# USBC_PD_SOURCING.net
KiCad netlist of a schematic drawn in Altium Designer
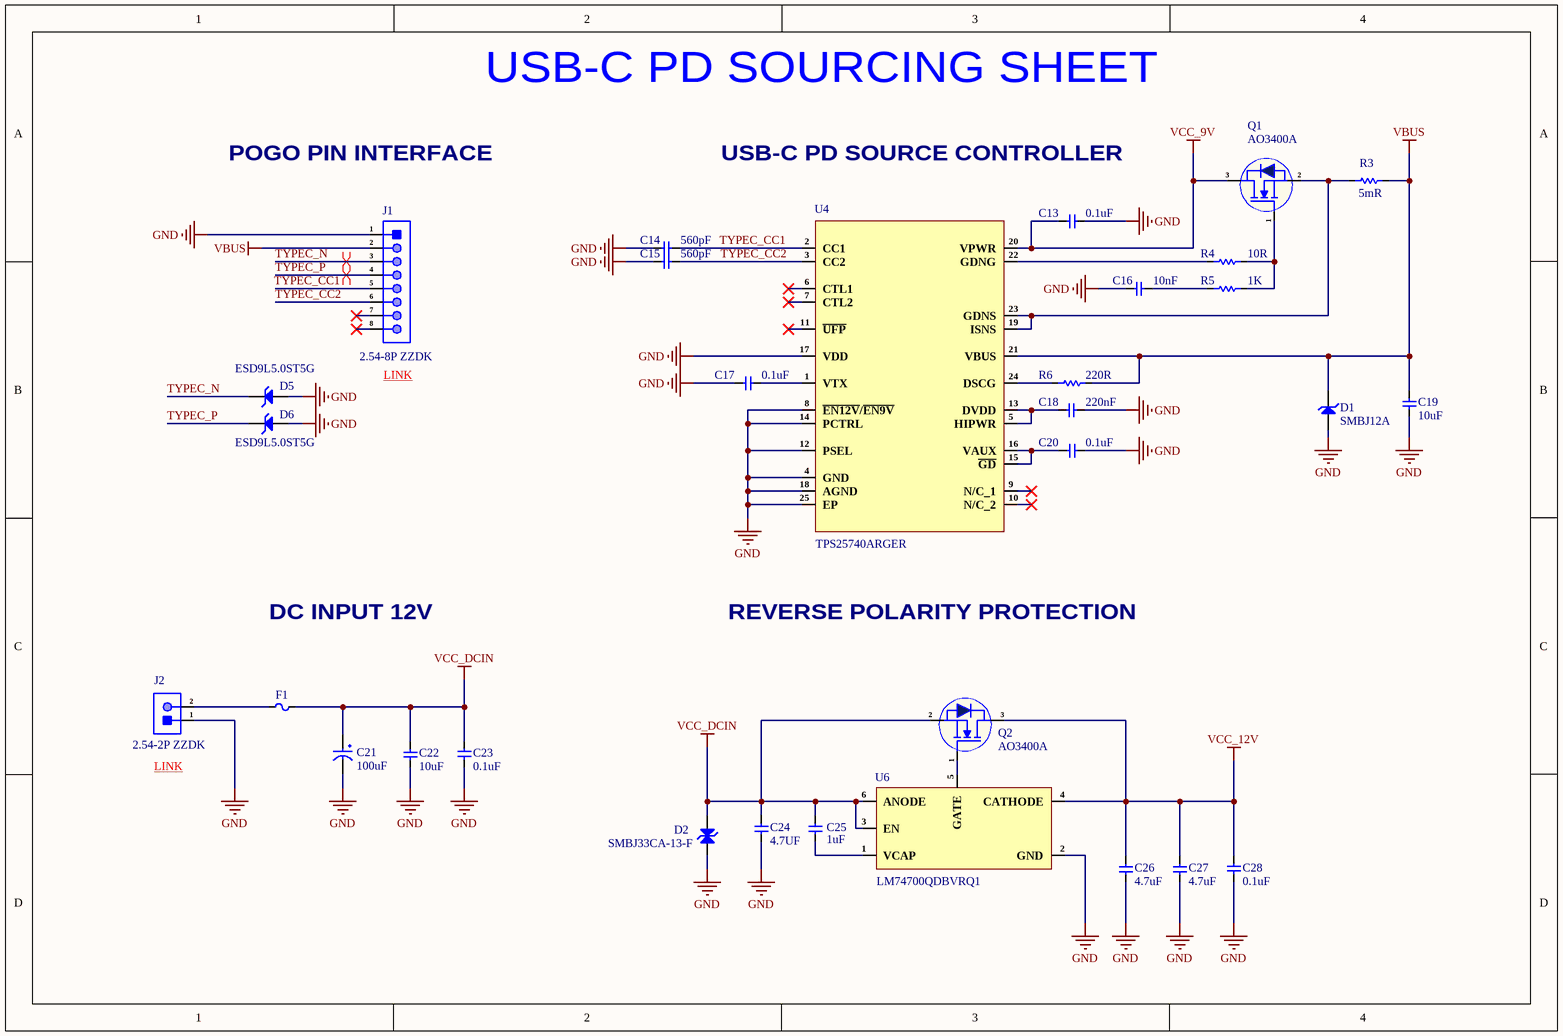
[diagram p0: USBC_PD_SOURCING.SchDoc]

(export (version "E")
  (design (tool "Eeschema 10.0.6"))
  (components
    (comp (ref "C13")
      (value "0.1uF")
      (footprint "Cap-0402")
      (description "CAP CER 0.1UF 50V X7R 0402")
      (fields
        (field (name "MANUFACTURER") "Samsung")
        (field (name "MANUFACTURER PART NUMBER") "CL05B104KB54PNC")
      )
      (libsource (lib "eSpark Libraries") (part "CL05B104KB54PNC"))
    )
    (comp (ref "C14")
      (value "560pF")
      (footprint "Cap-0402")
      (description "CAP CER 560PF 50V X7R 0402")
      (fields
        (field (name "MANUFACTURER") "Yageo")
        (field (name "MANUFACTURER PART NUMBER") "CC0402JRX7R9BB561")
      )
      (libsource (lib "eSpark Libraries") (part "CC0402JRX7R9BB561"))
    )
    (comp (ref "C15")
      (value "560pF")
      (footprint "Cap-0402")
      (description "CAP CER 560PF 50V X7R 0402")
      (fields
        (field (name "MANUFACTURER") "Yageo")
        (field (name "MANUFACTURER PART NUMBER") "CC0402JRX7R9BB561")
      )
      (libsource (lib "eSpark Libraries") (part "CC0402JRX7R9BB561"))
    )
    (comp (ref "C16")
      (value "10nF")
      (footprint "Cap-0402")
      (description "CAP CER 10000PF 50V X7R 0402")
      (fields
        (field (name "MANUFACTURER") "Yageo")
        (field (name "MANUFACTURER PART NUMBER") "CC0402KRX7R9BB103")
      )
      (libsource (lib "eSpark Libraries") (part "CC0402KRX7R9BB103"))
    )
    (comp (ref "C17")
      (value "0.1uF")
      (footprint "Cap-0402")
      (description "CAP CER 0.1UF 50V X7R 0402")
      (fields
        (field (name "MANUFACTURER") "Samsung")
        (field (name "MANUFACTURER PART NUMBER") "CL05B104KB54PNC")
      )
      (libsource (lib "eSpark Libraries") (part "CL05B104KB54PNC"))
    )
    (comp (ref "C18")
      (value "220nF")
      (footprint "Cap-0402")
      (description "CAP CER 0.22UF 25V X5R 0402")
      (fields
        (field (name "MANUFACTURER") "Yageo")
        (field (name "MANUFACTURER PART NUMBER") "CC0402KRX5R8BB224")
      )
      (libsource (lib "eSpark Libraries") (part "CC0402KRX5R8BB224"))
    )
    (comp (ref "C19")
      (value "10uF")
      (footprint "Cap-0805")
      (description "CAP CER 10UF 50V X5R 0805")
      (fields
        (field (name "MANUFACTURER") "Murata")
        (field (name "MANUFACTURER PART NUMBER") "GRM21BR61H106ME43L")
      )
      (libsource (lib "eSpark Libraries") (part "GRM21BR61H106ME43L"))
    )
    (comp (ref "C20")
      (value "0.1uF")
      (footprint "Cap-0402")
      (description "CAP CER 0.1UF 50V X7R 0402")
      (fields
        (field (name "MANUFACTURER") "Samsung")
        (field (name "MANUFACTURER PART NUMBER") "CL05B104KB54PNC")
      )
      (libsource (lib "eSpark Libraries") (part "CL05B104KB54PNC"))
    )
    (comp (ref "C21")
      (value "100uF")
      (footprint "Case-E")
      (description "CAP TANT 100UF 20% 25V 2917")
      (fields
        (field (name "MANUFACTURER") "Kyocera AVX")
        (field (name "MANUFACTURER PART NUMBER") "TAJE107M025RNJ")
      )
      (libsource (lib "eSpark Libraries") (part "TAJE107M025RNJ"))
    )
    (comp (ref "C22")
      (value "10uF")
      (footprint "Cap-0805")
      (description "CAP CER 10UF 50V X5R 0805")
      (fields
        (field (name "MANUFACTURER") "Murata")
        (field (name "MANUFACTURER PART NUMBER") "GRM21BR61H106ME43L")
      )
      (libsource (lib "eSpark Libraries") (part "GRM21BR61H106ME43L"))
    )
    (comp (ref "C23")
      (value "0.1uF")
      (footprint "Cap-0402")
      (description "CAP CER 0.1UF 50V X7R 0402")
      (fields
        (field (name "MANUFACTURER") "Samsung")
        (field (name "MANUFACTURER PART NUMBER") "CL05B104KB54PNC")
      )
      (libsource (lib "eSpark Libraries") (part "CL05B104KB54PNC"))
    )
    (comp (ref "C24")
      (value "4.7UF")
      (footprint "Cap-0603")
      (description "CAP CER 4.7UF 25V X5R 0603")
      (fields
        (field (name "MANUFACTURER") "Samsung")
        (field (name "MANUFACTURER PART NUMBER") "CL10A475KA8NQNC")
      )
      (libsource (lib "eSpark Libraries") (part "CL10A475KA8NQNC"))
    )
    (comp (ref "C25")
      (value "1uF")
      (footprint "Cap-0402")
      (description "CAP CER 1UF 25V X5R 0402")
      (fields
        (field (name "MANUFACTURER") "Yageo")
        (field (name "MANUFACTURER PART NUMBER") "CC0402KRX5R8BB105")
      )
      (libsource (lib "eSpark Libraries") (part "CC0402KRX5R8BB105"))
    )
    (comp (ref "C26")
      (value "4.7uF")
      (footprint "Cap-0805")
      (description "CAP CER 4.7UF 50V X5R 0805")
      (fields
        (field (name "MANUFACTURER") "Murata")
        (field (name "MANUFACTURER PART NUMBER") "GRM21BR61H475KE51L")
      )
      (libsource (lib "eSpark Libraries") (part "GRM21BR61H475KE51L"))
    )
    (comp (ref "C27")
      (value "4.7uF")
      (footprint "Cap-0805")
      (description "CAP CER 4.7UF 50V X5R 0805")
      (fields
        (field (name "MANUFACTURER") "Murata")
        (field (name "MANUFACTURER PART NUMBER") "GRM21BR61H475KE51L")
      )
      (libsource (lib "eSpark Libraries") (part "GRM21BR61H475KE51L"))
    )
    (comp (ref "C28")
      (value "0.1uF")
      (footprint "Cap-0402")
      (description "CAP CER 0.1UF 50V X7R 0402")
      (fields
        (field (name "MANUFACTURER") "Samsung")
        (field (name "MANUFACTURER PART NUMBER") "CL05B104KB54PNC")
      )
      (libsource (lib "eSpark Libraries") (part "CL05B104KB54PNC"))
    )
    (comp (ref "D1")
      (value "SMBJ12A")
      (footprint "SMB_")
      (description "TVS DIODE 12VWM 19.9VC DO214AA")
      (fields (field (name "LCSC PART NUMBER") "C151251") (field (name "MANUFACTURER") "Littelfuse"))
      (libsource (lib "eSpark Libraries") (part "SMBJ12A"))
    )
    (comp (ref "D2")
      (value "SMBJ33CA-13-F")
      (footprint "SMB Bi Directional")
      (description "TVS DIODE 33VWM 53.3VC SMB")
      (fields (field (name "MANUFACTURER") "Diodes") (field (name "LCSC PART NUMBER") "C135068"))
      (libsource (lib "eSpark Libraries") (part "SMBJ33CA-13-F"))
    )
    (comp (ref "D5")
      (value "ESD9L5.0ST5G")
      (footprint "SOD-923.")
      (fields (field (name "MANUFACTURER") "ON Semiconductor") (field (name "LCSC PART NUMBER") "C82326"))
      (libsource (lib "eSpark Libraries") (part "ESD9L5.0ST5G"))
    )
    (comp (ref "D6")
      (value "ESD9L5.0ST5G")
      (footprint "SOD-923.")
      (description "TVS DIODE 5V 9.8V SOD923")
      (fields (field (name "MANUFACTURER") "ON Semiconductor") (field (name "LCSC PART NUMBER") "C82326"))
      (libsource (lib "eSpark Libraries") (part "ESD9L5.0ST5G"))
    )
    (comp (ref "F1")
      (value "BSMD1812-300-24V")
      (footprint "Fuse-1812_")
      (description "24V 3A 40A 6A 1812 Resettable Fuses ROHS")
      (fields (field (name "LCSC PART NUMBER") "C7500481") (field (name "MANUFACTURER") "BHFUSE"))
      (libsource (lib "eSpark Libraries") (part "BSMD1812-300-24V"))
    )
    (comp (ref "J1")
      (value "2.54-8P ZZDK")
      (footprint "2.54-8P ZZDK")
      (fields (field (name "MANUFACTURER") "SHOU HAN") (field (name "LCSC PART NUMBER") "C18185655"))
      (libsource (lib "DOCK_ESP32_v1.0") (part "2.54-8P ZZDK"))
    )
    (comp (ref "J2")
      (value "2.54-2P ZZDK")
      (footprint "2.54-2P ZZDK")
      (fields (field (name "MANUFACTURER") "SHOU HAN") (field (name "LCSC PART NUMBER") "C18185649"))
      (libsource (lib "eSpark Libraries") (part "2.54-2P ZZDK"))
    )
    (comp (ref "Q1")
      (value "AO3400A")
      (footprint "sot-23")
      (description "30V 5.8A 32mΩ@10V,5.8A 1.4W 1.4V@250uA N Channel SOT-23 MOSFETs ROHS")
      (fields (field (name "MANUFACTURER") "BORN") (field (name "LCSC PART NUMBER") "C344010"))
      (libsource (lib "eSpark Libraries") (part "AO3400A"))
    )
    (comp (ref "Q2")
      (value "AO3400A")
      (footprint "sot-23")
      (description "30V 5.8A 32mΩ@10V,5.8A 1.4W 1.4V@250uA N Channel SOT-23 MOSFETs ROHS")
      (fields (field (name "MANUFACTURER") "BORN") (field (name "LCSC PART NUMBER") "C344010"))
      (libsource (lib "eSpark Libraries") (part "AO3400A"))
    )
    (comp (ref "R3")
      (value "5mR")
      (footprint "RES-2512")
      (description "RES 0.005 OHM 1% 2W 2512")
      (fields (field (name "LCSC PART NUMBER") "C309526") (field (name "MANUFACTURER") "Yageo"))
      (libsource (lib "eSpark Libraries") (part "PA2512FKF7W0R005E"))
    )
    (comp (ref "R4")
      (value "10R")
      (footprint "Res-0603")
      (description "RES SMD 10 OHM 1% 1/10W 0603")
      (fields
        (field (name "MANUFACTURER") "Yageo")
        (field (name "MANUFACTURER PART NUMBER") "RC0603FR-0710RL")
      )
      (libsource (lib "eSpark Libraries") (part "RC0603FR-0710RL"))
    )
    (comp (ref "R5")
      (value "1K")
      (footprint "Res-0402")
      (description "RES SMD 1K OHM 1% 1/5W 0402")
      (fields
        (field (name "MANUFACTURER") "Vishay Dale")
        (field (name "MANUFACTURER PART NUMBER") "CRCW04021K00FKEDHP")
      )
      (libsource (lib "eSpark Libraries") (part "CRCW04021K00FKEDHP"))
    )
    (comp (ref "R6")
      (value "220R")
      (footprint "Res-0402")
      (description "RES 220 OHM 1% 1/16W 0402")
      (fields (field (name "LCSC PART NUMBER") "C112291") (field (name "MANUFACTURER") "Yageo"))
      (libsource (lib "eSpark Libraries") (part "RC0402FR-07220RL"))
    )
    (comp (ref "U4")
      (value "TPS25740ARGER")
      (footprint "QFN50P400X400X100-25N-D")
      (description "TPS25740A USB Type-C Rev 1.2 and USB PD 2.0 Source Controller (5V/9V/15V)")
      (fields (field (name "LCSC PART NUMBER") "C544309"))
      (libsource (lib "DOCK_ESP32_v1.0") (part "TPS25740ARGER"))
    )
    (comp (ref "U6")
      (value "LM74700QDBVRQ1")
      (footprint "SOT-23-6")
      (description "OR Controller N+1 ORing Controller N-Channel 1:1 SOT-23-6")
      (fields (field (name "MANUFACTURER") "Texas Instruments") (field (name "LCSC PART NUMBER") "C2941042"))
      (libsource (lib "eSpark Libraries") (part "LM74700QDBVRQ1"))
    )
  )
  (nets
    (net (code "1") (name "/TYPEC_CC1") (class "Default")
      (node (ref "C14") (pin "2") (pinfunction "2_2") (pintype "passive"))
      (node (ref "J1") (pin "5") (pinfunction "5_5") (pintype "passive"))
      (node (ref "U4") (pin "2") (pinfunction "CC1_2") (pintype "passive"))
    )
    (net (code "2") (name "/TYPEC_CC2") (class "Default")
      (node (ref "C15") (pin "2") (pinfunction "2_2") (pintype "passive"))
      (node (ref "J1") (pin "6") (pinfunction "6_6") (pintype "passive"))
      (node (ref "U4") (pin "3") (pinfunction "CC2_3") (pintype "passive"))
    )
    (net (code "3") (name "/TYPEC_N") (class "Default")
      (node (ref "D5") (pin "1") (pinfunction "K_1") (pintype "passive"))
      (node (ref "J1") (pin "3") (pinfunction "3_3") (pintype "passive"))
    )
    (net (code "4") (name "/TYPEC_P") (class "Default")
      (node (ref "D6") (pin "1") (pinfunction "K_1") (pintype "passive"))
      (node (ref "J1") (pin "4") (pinfunction "4_4") (pintype "passive"))
    )
    (net (code "5") (name "GND") (class "Default")
      (node (ref "C13") (pin "1") (pinfunction "1_1") (pintype "passive"))
      (node (ref "C14") (pin "1") (pinfunction "1_1") (pintype "passive"))
      (node (ref "C15") (pin "1") (pinfunction "1_1") (pintype "passive"))
      (node (ref "C16") (pin "1") (pinfunction "1_1") (pintype "passive"))
      (node (ref "C17") (pin "2") (pinfunction "2_2") (pintype "passive"))
      (node (ref "C18") (pin "2") (pinfunction "2_2") (pintype "passive"))
      (node (ref "C19") (pin "1") (pinfunction "1_1") (pintype "passive"))
      (node (ref "C20") (pin "1") (pinfunction "1_1") (pintype "passive"))
      (node (ref "C21") (pin "2") (pinfunction "2_2") (pintype "passive"))
      (node (ref "C22") (pin "1") (pinfunction "1_1") (pintype "passive"))
      (node (ref "C23") (pin "2") (pinfunction "2_2") (pintype "passive"))
      (node (ref "C24") (pin "1") (pinfunction "1_1") (pintype "passive"))
      (node (ref "C26") (pin "1") (pinfunction "1_1") (pintype "passive"))
      (node (ref "C27") (pin "1") (pinfunction "1_1") (pintype "passive"))
      (node (ref "C28") (pin "2") (pinfunction "2_2") (pintype "passive"))
      (node (ref "D1") (pin "1") (pinfunction "A_1") (pintype "passive"))
      (node (ref "D2") (pin "1") (pinfunction "A_1") (pintype "passive"))
      (node (ref "D5") (pin "2") (pinfunction "A_2") (pintype "passive"))
      (node (ref "D6") (pin "2") (pinfunction "A_2") (pintype "passive"))
      (node (ref "J1") (pin "1") (pinfunction "1_1") (pintype "passive"))
      (node (ref "J2") (pin "1") (pinfunction "1_1") (pintype "passive"))
      (node (ref "U4") (pin "12") (pinfunction "PSEL_12") (pintype "passive"))
      (node (ref "U4") (pin "14") (pinfunction "PCTRL_14") (pintype "passive"))
      (node (ref "U4") (pin "17") (pinfunction "VDD_17") (pintype "passive"))
      (node (ref "U4") (pin "18") (pinfunction "AGND_18") (pintype "passive"))
      (node (ref "U4") (pin "25") (pinfunction "EP_25") (pintype "passive"))
      (node (ref "U4") (pin "4") (pinfunction "GND_4") (pintype "passive"))
      (node (ref "U4") (pin "8") (pinfunction "~{EN12V}/~{EN9V}_8") (pintype "passive"))
      (node (ref "U6") (pin "2") (pinfunction "GND_2") (pintype "passive"))
    )
    (net (code "6") (name "Net-(C16-Pad2)") (class "Default")
      (node (ref "C16") (pin "2") (pinfunction "2_2") (pintype "passive"))
      (node (ref "R5") (pin "1") (pinfunction "1_1") (pintype "passive"))
    )
    (net (code "7") (name "Net-(F1-Pad1)") (class "Default")
      (node (ref "F1") (pin "1") (pinfunction "1_1") (pintype "passive"))
      (node (ref "J2") (pin "2") (pinfunction "2_2") (pintype "passive"))
    )
    (net (code "8") (name "Net-(Q1-G)") (class "Default")
      (node (ref "Q1") (pin "1") (pinfunction "G_1") (pintype "passive"))
      (node (ref "R4") (pin "2") (pinfunction "2_2") (pintype "passive"))
      (node (ref "R5") (pin "2") (pinfunction "2_2") (pintype "passive"))
    )
    (net (code "9") (name "Net-(Q1-S)") (class "Default")
      (node (ref "Q1") (pin "2") (pinfunction "S_2") (pintype "passive"))
      (node (ref "R3") (pin "1") (pinfunction "1_1") (pintype "passive"))
      (node (ref "U4") (pin "19") (pinfunction "ISNS_19") (pintype "passive"))
      (node (ref "U4") (pin "23") (pinfunction "GDNS_23") (pintype "passive"))
    )
    (net (code "10") (name "Net-(Q2-G)") (class "Default")
      (node (ref "Q2") (pin "1") (pinfunction "G_1") (pintype "passive"))
      (node (ref "U6") (pin "5") (pinfunction "GATE_5") (pintype "passive"))
    )
    (net (code "11") (name "Net-(U4-DSCG)") (class "Default")
      (node (ref "R6") (pin "1") (pinfunction "1_1") (pintype "passive"))
      (node (ref "U4") (pin "24") (pinfunction "DSCG_24") (pintype "passive"))
    )
    (net (code "12") (name "Net-(U4-DVDD)") (class "Default")
      (node (ref "C18") (pin "1") (pinfunction "1_1") (pintype "passive"))
      (node (ref "U4") (pin "13") (pinfunction "DVDD_13") (pintype "passive"))
      (node (ref "U4") (pin "5") (pinfunction "HIPWR_5") (pintype "passive"))
    )
    (net (code "13") (name "Net-(U4-GDNG)") (class "Default")
      (node (ref "R4") (pin "1") (pinfunction "1_1") (pintype "passive"))
      (node (ref "U4") (pin "22") (pinfunction "GDNG_22") (pintype "passive"))
    )
    (net (code "14") (name "Net-(U4-VAUX)") (class "Default")
      (node (ref "C20") (pin "2") (pinfunction "2_2") (pintype "passive"))
      (node (ref "U4") (pin "15") (pinfunction "~{GD}_15") (pintype "passive"))
      (node (ref "U4") (pin "16") (pinfunction "VAUX_16") (pintype "passive"))
    )
    (net (code "15") (name "Net-(U4-VTX)") (class "Default")
      (node (ref "C17") (pin "1") (pinfunction "1_1") (pintype "passive"))
      (node (ref "U4") (pin "1") (pinfunction "VTX_1") (pintype "passive"))
    )
    (net (code "16") (name "Net-(U6-VCAP)") (class "Default")
      (node (ref "C25") (pin "1") (pinfunction "1_1") (pintype "passive"))
      (node (ref "U6") (pin "1") (pinfunction "VCAP_1") (pintype "passive"))
    )
    (net (code "17") (name "VBUS") (class "Default")
      (node (ref "C19") (pin "2") (pinfunction "2_2") (pintype "passive"))
      (node (ref "D1") (pin "2") (pinfunction "K_2") (pintype "passive"))
      (node (ref "J1") (pin "2") (pinfunction "2_2") (pintype "passive"))
      (node (ref "R3") (pin "2") (pinfunction "2_2") (pintype "passive"))
      (node (ref "R6") (pin "2") (pinfunction "2_2") (pintype "passive"))
      (node (ref "U4") (pin "21") (pinfunction "VBUS_21") (pintype "passive"))
    )
    (net (code "18") (name "VCC_9V") (class "Default")
      (node (ref "C13") (pin "2") (pinfunction "2_2") (pintype "passive"))
      (node (ref "Q1") (pin "3") (pinfunction "D_3") (pintype "passive"))
      (node (ref "U4") (pin "20") (pinfunction "VPWR_20") (pintype "passive"))
    )
    (net (code "19") (name "VCC_12V") (class "Default")
      (node (ref "C26") (pin "2") (pinfunction "2_2") (pintype "passive"))
      (node (ref "C27") (pin "2") (pinfunction "2_2") (pintype "passive"))
      (node (ref "C28") (pin "1") (pinfunction "1_1") (pintype "passive"))
      (node (ref "Q2") (pin "3") (pinfunction "D_3") (pintype "passive"))
      (node (ref "U6") (pin "4") (pinfunction "CATHODE_4") (pintype "passive"))
    )
    (net (code "20") (name "VCC_DCIN") (class "Default")
      (node (ref "C21") (pin "1") (pinfunction "1_1") (pintype "passive"))
      (node (ref "C22") (pin "2") (pinfunction "2_2") (pintype "passive"))
      (node (ref "C23") (pin "1") (pinfunction "1_1") (pintype "passive"))
      (node (ref "C24") (pin "2") (pinfunction "2_2") (pintype "passive"))
      (node (ref "C25") (pin "2") (pinfunction "2_2") (pintype "passive"))
      (node (ref "D2") (pin "2") (pinfunction "K_2") (pintype "passive"))
      (node (ref "F1") (pin "2") (pinfunction "2_2") (pintype "passive"))
      (node (ref "Q2") (pin "2") (pinfunction "S_2") (pintype "passive"))
      (node (ref "U6") (pin "3") (pinfunction "EN_3") (pintype "passive"))
      (node (ref "U6") (pin "6") (pinfunction "ANODE_6") (pintype "passive"))
    )
    (net (code "21") (name "unconnected-(J1-Pad7)") (class "Default")
      (node (ref "J1") (pin "7") (pinfunction "7_7") (pintype "passive+no_connect"))
    )
    (net (code "22") (name "unconnected-(J1-Pad8)") (class "Default")
      (node (ref "J1") (pin "8") (pinfunction "8_8") (pintype "passive+no_connect"))
    )
    (net (code "23") (name "unconnected-(U4-CTL1-Pad6)") (class "Default")
      (node (ref "U4") (pin "6") (pinfunction "CTL1_6") (pintype "passive+no_connect"))
    )
    (net (code "24") (name "unconnected-(U4-CTL2-Pad7)") (class "Default")
      (node (ref "U4") (pin "7") (pinfunction "CTL2_7") (pintype "passive+no_connect"))
    )
    (net (code "25") (name "unconnected-(U4-N{slash}C_1-Pad9)") (class "Default")
      (node (ref "U4") (pin "9") (pinfunction "N/C_1_9") (pintype "passive+no_connect"))
    )
    (net (code "26") (name "unconnected-(U4-N{slash}C_2-Pad10)") (class "Default")
      (node (ref "U4") (pin "10") (pinfunction "N/C_2_10") (pintype "passive+no_connect"))
    )
    (net (code "27") (name "unconnected-(U4-~{UFP}-Pad11)") (class "Default")
      (node (ref "U4") (pin "11") (pinfunction "~{UFP}_11") (pintype "passive+no_connect"))
    )
  )
)
